# SCH_pcb-2_2025-06-04.net
KiCad netlist of a schematic drawn in EasyEDA
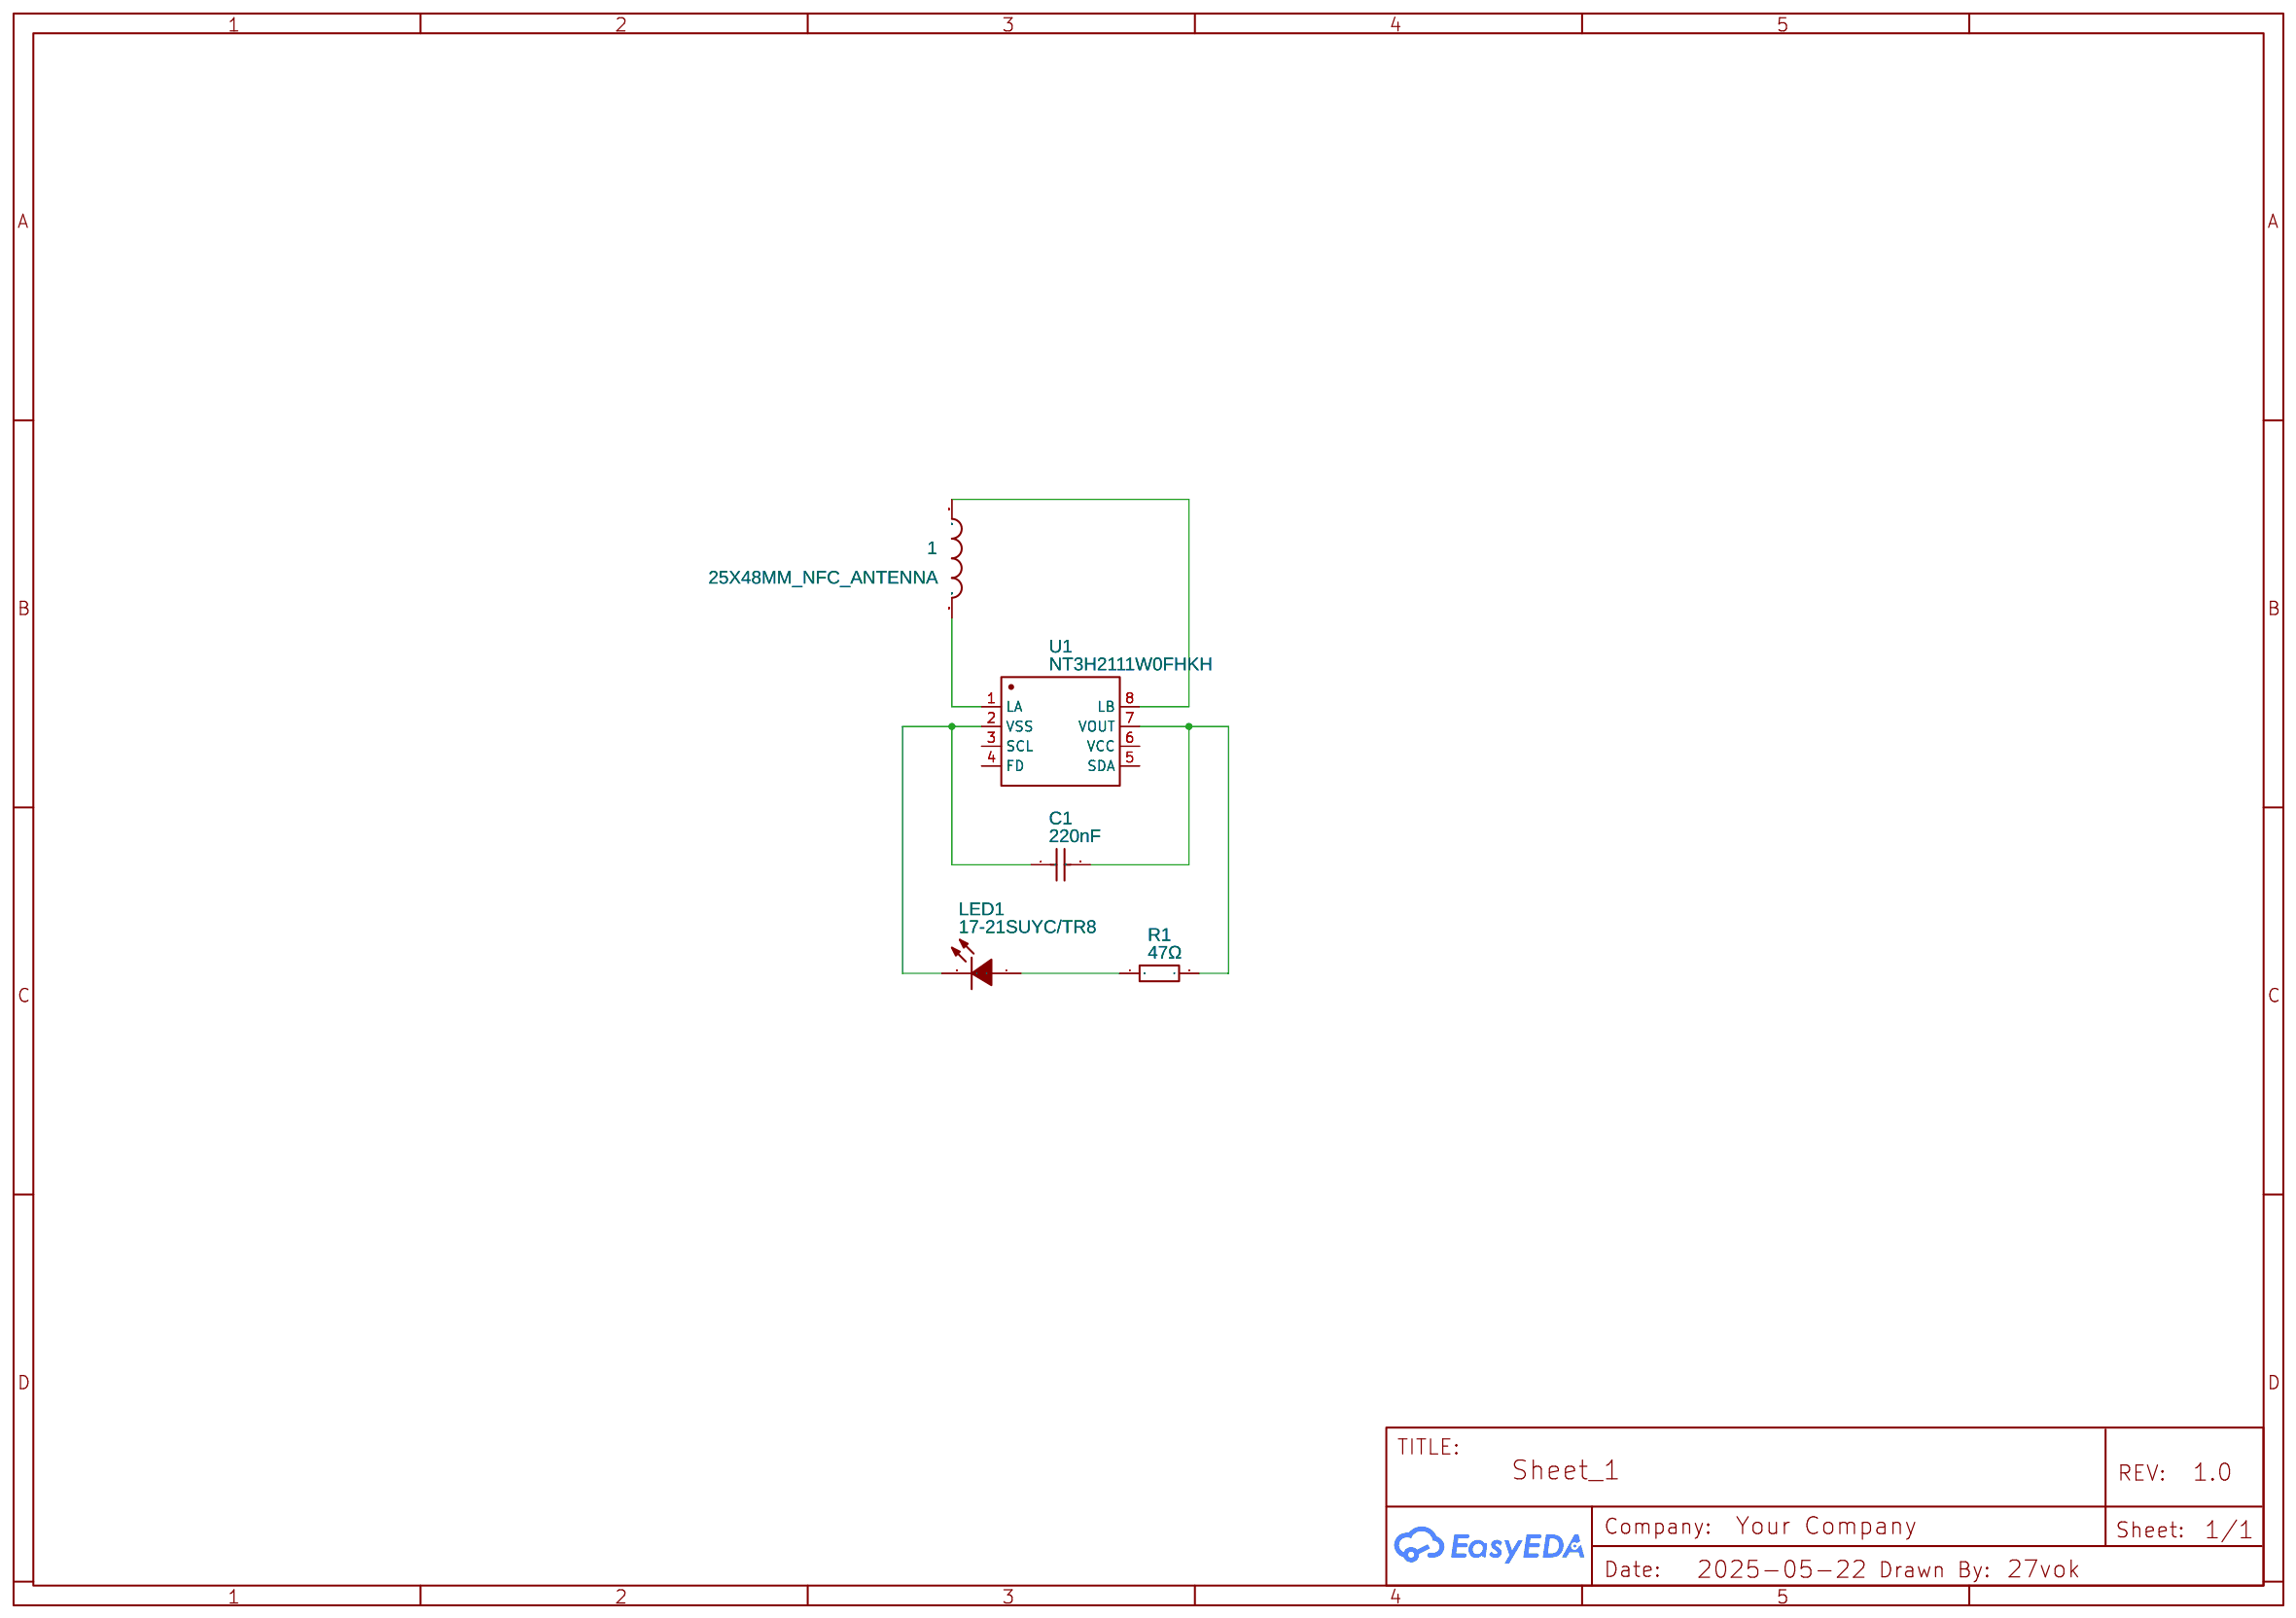
[diagram p0: schematic sheet]

(export (version "E")
  (design (tool "Eeschema 10.0.6"))
  (components
    (comp (ref "1") (value "25X48MM_NFC_ANTENNA") (libsource (lib "") (part "25X48MM_NFC_ANTENNA")))
    (comp (ref "C1")
      (value "220nF")
      (fields
        (field (name "Manufacturer Part") "CL10B224KA8NNNC")
        (field (name "Manufacturer") "SAMSUNG(三星)")
      )
      (libsource (lib "") (part "CL10B224KA8NNNC"))
    )
    (comp (ref "LED1")
      (value "17-21SUYC/TR8")
      (fields (field (name "Manufacturer Part") "KT-0805黄灯") (field (name "Manufacturer") "KENTO"))
      (libsource (lib "") (part "17-21SUYC/TR8"))
    )
    (comp (ref "R1")
      (value "47Ω")
      (fields
        (field (name "Manufacturer Part") "0603WAF470JT5E")
        (field (name "Manufacturer") "UNI-ROYAL(厚声)")
      )
      (libsource (lib "") (part "0603WAF470JT5E"))
    )
    (comp (ref "U1")
      (value "NT3H2111W0FHKH")
      (fields (field (name "Manufacturer") "NXP(恩智浦)"))
      (libsource (lib "") (part "NT3H2111W0FHKH"))
    )
  )
  (nets
    (net (code "1") (name "Net-(LED1-+)") (class "Default")
      (node (ref "LED1") (pin "1") (pinfunction "+_1") (pintype "unspecified"))
      (node (ref "R1") (pin "1") (pinfunction "1_1") (pintype "input"))
    )
    (net (code "2") (name "Net-(LED1--)") (class "Default")
      (node (ref "C1") (pin "1") (pinfunction "1_1") (pintype "input"))
      (node (ref "LED1") (pin "2") (pinfunction "-_2") (pintype "unspecified"))
      (node (ref "U1") (pin "2") (pinfunction "VSS_2") (pintype "unspecified"))
    )
    (net (code "3") (name "Net-(U1-LA)") (class "Default")
      (node (ref "1") (pin "P$2") (pinfunction "P$2_P$2") (pintype "bidirectional"))
      (node (ref "U1") (pin "1") (pinfunction "LA_1") (pintype "unspecified"))
    )
    (net (code "4") (name "Net-(U1-LB)") (class "Default")
      (node (ref "1") (pin "P$1") (pinfunction "P$1_P$1") (pintype "bidirectional"))
      (node (ref "U1") (pin "8") (pinfunction "LB_8") (pintype "unspecified"))
    )
    (net (code "5") (name "Net-(U1-VOUT)") (class "Default")
      (node (ref "C1") (pin "2") (pinfunction "2_2") (pintype "input"))
      (node (ref "R1") (pin "2") (pinfunction "2_2") (pintype "input"))
      (node (ref "U1") (pin "7") (pinfunction "VOUT_7") (pintype "unspecified"))
    )
    (net (code "6") (name "unconnected-(U1-FD-Pad4)") (class "Default")
      (node (ref "U1") (pin "4") (pinfunction "FD_4") (pintype "unspecified"))
    )
    (net (code "7") (name "unconnected-(U1-SCL-Pad3)") (class "Default")
      (node (ref "U1") (pin "3") (pinfunction "SCL_3") (pintype "unspecified"))
    )
    (net (code "8") (name "unconnected-(U1-SDA-Pad5)") (class "Default")
      (node (ref "U1") (pin "5") (pinfunction "SDA_5") (pintype "unspecified"))
    )
    (net (code "9") (name "unconnected-(U1-VCC-Pad6)") (class "Default")
      (node (ref "U1") (pin "6") (pinfunction "VCC_6") (pintype "unspecified"))
    )
  )
)
